# NMNSH_F-16_Lighting_Controller.net
KiCad netlist of a schematic drawn in EAGLE
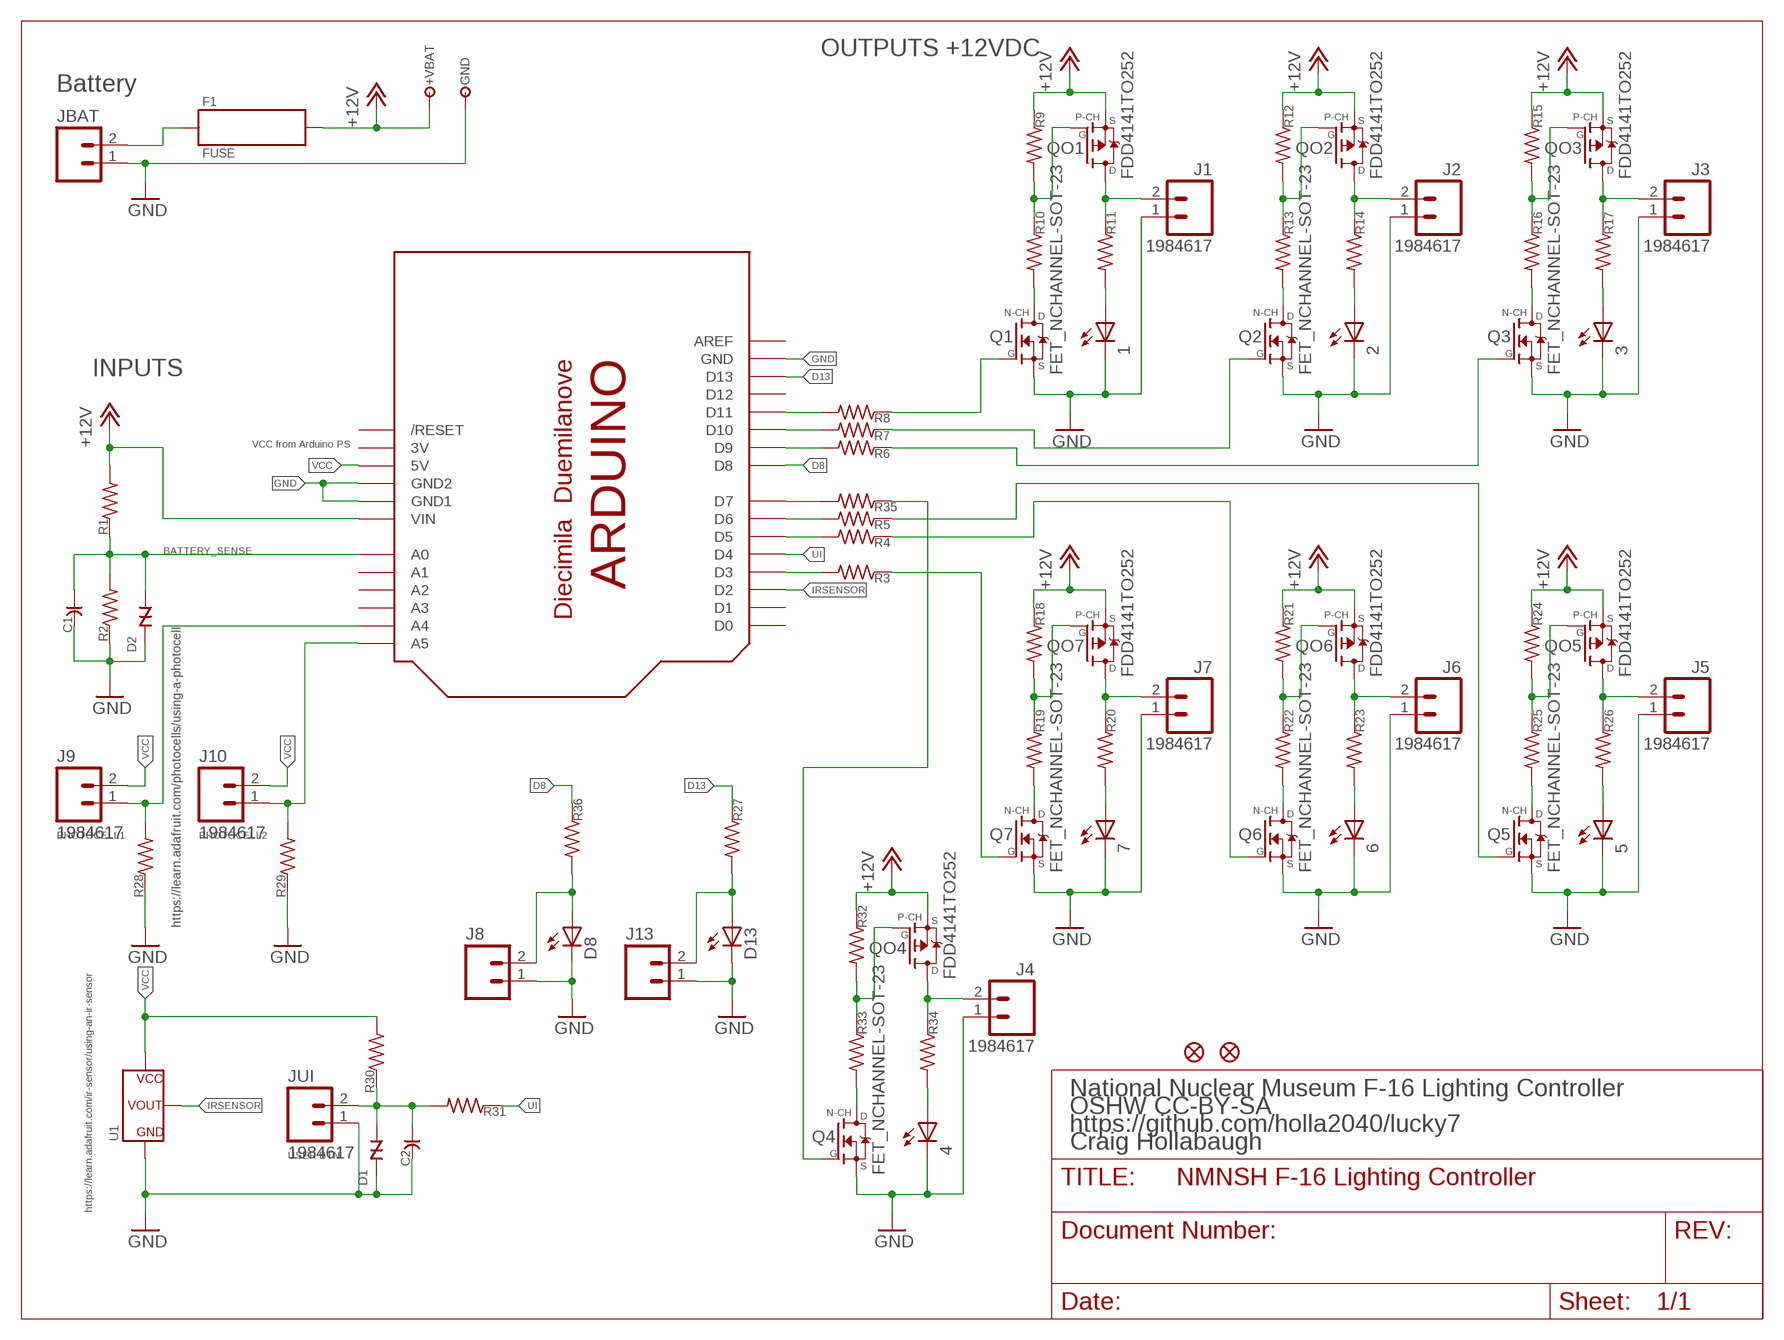
[diagram p0: schematic, sheet 1]

(export (version "E")
  (design (tool "Eeschema 10.0.6"))
  (components
    (comp (ref "+VBAT")
      (value "TESTPOINTTHRU")
      (footprint "eagle-import:TPTHRU")
      (libsource (lib "eagle-import") (part "TESTPOINTTHRU"))
    )
    (comp (ref "1")
      (value "LEDCHIP-LED0805")
      (footprint "eagle-import:CHIP-LED0805")
      (libsource (lib "eagle-import") (part "LEDCHIP-LED0805"))
    )
    (comp (ref "2")
      (value "LEDCHIP-LED0805")
      (footprint "eagle-import:CHIP-LED0805")
      (libsource (lib "eagle-import") (part "LEDCHIP-LED0805"))
    )
    (comp (ref "3")
      (value "LEDCHIP-LED0805")
      (footprint "eagle-import:CHIP-LED0805")
      (libsource (lib "eagle-import") (part "LEDCHIP-LED0805"))
    )
    (comp (ref "4")
      (value "LEDCHIP-LED0805")
      (footprint "eagle-import:CHIP-LED0805")
      (libsource (lib "eagle-import") (part "LEDCHIP-LED0805"))
    )
    (comp (ref "5")
      (value "LEDCHIP-LED0805")
      (footprint "eagle-import:CHIP-LED0805")
      (libsource (lib "eagle-import") (part "LEDCHIP-LED0805"))
    )
    (comp (ref "6")
      (value "LEDCHIP-LED0805")
      (footprint "eagle-import:CHIP-LED0805")
      (libsource (lib "eagle-import") (part "LEDCHIP-LED0805"))
    )
    (comp (ref "7")
      (value "LEDCHIP-LED0805")
      (footprint "eagle-import:CHIP-LED0805")
      (libsource (lib "eagle-import") (part "LEDCHIP-LED0805"))
    )
    (comp (ref "C1")
      (value "C-USC0603")
      (footprint "eagle-import:C0603")
      (libsource (lib "eagle-import") (part "C-USC0603"))
    )
    (comp (ref "C2")
      (value "C-USC0603")
      (footprint "eagle-import:C0603")
      (libsource (lib "eagle-import") (part "C-USC0603"))
    )
    (comp (ref "D1")
      (value "TVS0603")
      (footprint "eagle-import:TVS-0603")
      (libsource (lib "eagle-import") (part "TVS0603"))
    )
    (comp (ref "D2")
      (value "TVS0603")
      (footprint "eagle-import:TVS-0603")
      (libsource (lib "eagle-import") (part "TVS0603"))
    )
    (comp (ref "D8")
      (value "LEDCHIP-LED0805")
      (footprint "eagle-import:CHIP-LED0805")
      (libsource (lib "eagle-import") (part "LEDCHIP-LED0805"))
    )
    (comp (ref "D13")
      (value "LEDCHIP-LED0805")
      (footprint "eagle-import:CHIP-LED0805")
      (libsource (lib "eagle-import") (part "LEDCHIP-LED0805"))
    )
    (comp (ref "F1")
      (value "FUSE")
      (footprint "eagle-import:FUSE-3557-2")
      (libsource (lib "eagle-import") (part "FUSE"))
    )
    (comp (ref "GND")
      (value "TESTPOINTTHRU")
      (footprint "eagle-import:TPTHRU")
      (libsource (lib "eagle-import") (part "TESTPOINTTHRU"))
    )
    (comp (ref "J1")
      (value "1984617")
      (footprint "eagle-import:1984617")
      (libsource (lib "eagle-import") (part "1984617"))
    )
    (comp (ref "J2")
      (value "1984617")
      (footprint "eagle-import:1984617")
      (libsource (lib "eagle-import") (part "1984617"))
    )
    (comp (ref "J3")
      (value "1984617")
      (footprint "eagle-import:1984617")
      (libsource (lib "eagle-import") (part "1984617"))
    )
    (comp (ref "J4")
      (value "1984617")
      (footprint "eagle-import:1984617")
      (libsource (lib "eagle-import") (part "1984617"))
    )
    (comp (ref "J5")
      (value "1984617")
      (footprint "eagle-import:1984617")
      (libsource (lib "eagle-import") (part "1984617"))
    )
    (comp (ref "J6")
      (value "1984617")
      (footprint "eagle-import:1984617")
      (libsource (lib "eagle-import") (part "1984617"))
    )
    (comp (ref "J7")
      (value "1984617")
      (footprint "eagle-import:1984617")
      (libsource (lib "eagle-import") (part "1984617"))
    )
    (comp (ref "J8")
      (value "M02-0.1")
      (footprint "eagle-import:1X02")
      (libsource (lib "eagle-import") (part "M02-0.1"))
    )
    (comp (ref "J9")
      (value "1984617")
      (footprint "eagle-import:1984617")
      (libsource (lib "eagle-import") (part "1984617"))
    )
    (comp (ref "J10")
      (value "1984617")
      (footprint "eagle-import:1984617")
      (libsource (lib "eagle-import") (part "1984617"))
    )
    (comp (ref "J13")
      (value "M02-0.1")
      (footprint "eagle-import:1X02")
      (libsource (lib "eagle-import") (part "M02-0.1"))
    )
    (comp (ref "JBAT")
      (value "M02-6.35MM")
      (footprint "eagle-import:OSTT702")
      (libsource (lib "eagle-import") (part "M02-6.35MM"))
    )
    (comp (ref "JP1")
      (value "FIDUCIAL1X2")
      (footprint "eagle-import:FIDUCIAL-1X2")
      (libsource (lib "eagle-import") (part "FIDUCIAL1X2"))
    )
    (comp (ref "JP2")
      (value "FIDUCIAL1X2")
      (footprint "eagle-import:FIDUCIAL-1X2")
      (libsource (lib "eagle-import") (part "FIDUCIAL1X2"))
    )
    (comp (ref "JUI")
      (value "1984617")
      (footprint "eagle-import:1984617")
      (libsource (lib "eagle-import") (part "1984617"))
    )
    (comp (ref "Q1")
      (value "FET_NCHANNEL-SOT-23")
      (footprint "eagle-import:SOT-23")
      (libsource (lib "eagle-import") (part "FET_NCHANNEL-SOT-23"))
    )
    (comp (ref "Q2")
      (value "FET_NCHANNEL-SOT-23")
      (footprint "eagle-import:SOT-23")
      (libsource (lib "eagle-import") (part "FET_NCHANNEL-SOT-23"))
    )
    (comp (ref "Q3")
      (value "FET_NCHANNEL-SOT-23")
      (footprint "eagle-import:SOT-23")
      (libsource (lib "eagle-import") (part "FET_NCHANNEL-SOT-23"))
    )
    (comp (ref "Q4")
      (value "FET_NCHANNEL-SOT-23")
      (footprint "eagle-import:SOT-23")
      (libsource (lib "eagle-import") (part "FET_NCHANNEL-SOT-23"))
    )
    (comp (ref "Q5")
      (value "FET_NCHANNEL-SOT-23")
      (footprint "eagle-import:SOT-23")
      (libsource (lib "eagle-import") (part "FET_NCHANNEL-SOT-23"))
    )
    (comp (ref "Q6")
      (value "FET_NCHANNEL-SOT-23")
      (footprint "eagle-import:SOT-23")
      (libsource (lib "eagle-import") (part "FET_NCHANNEL-SOT-23"))
    )
    (comp (ref "Q7")
      (value "FET_NCHANNEL-SOT-23")
      (footprint "eagle-import:SOT-23")
      (libsource (lib "eagle-import") (part "FET_NCHANNEL-SOT-23"))
    )
    (comp (ref "QO1")
      (value "FDD4141TO252")
      (footprint "eagle-import:TO252")
      (libsource (lib "eagle-import") (part "FDD4141TO252"))
    )
    (comp (ref "QO2")
      (value "FDD4141TO252")
      (footprint "eagle-import:TO252")
      (libsource (lib "eagle-import") (part "FDD4141TO252"))
    )
    (comp (ref "QO3")
      (value "FDD4141TO252")
      (footprint "eagle-import:TO252")
      (libsource (lib "eagle-import") (part "FDD4141TO252"))
    )
    (comp (ref "QO4")
      (value "FDD4141TO252")
      (footprint "eagle-import:TO252")
      (libsource (lib "eagle-import") (part "FDD4141TO252"))
    )
    (comp (ref "QO5")
      (value "FDD4141TO252")
      (footprint "eagle-import:TO252")
      (libsource (lib "eagle-import") (part "FDD4141TO252"))
    )
    (comp (ref "QO6")
      (value "FDD4141TO252")
      (footprint "eagle-import:TO252")
      (libsource (lib "eagle-import") (part "FDD4141TO252"))
    )
    (comp (ref "QO7")
      (value "FDD4141TO252")
      (footprint "eagle-import:TO252")
      (libsource (lib "eagle-import") (part "FDD4141TO252"))
    )
    (comp (ref "R1")
      (value "R-US_R0603")
      (footprint "eagle-import:R0603")
      (libsource (lib "eagle-import") (part "R-US_R0603"))
    )
    (comp (ref "R2")
      (value "R-US_R0603")
      (footprint "eagle-import:R0603")
      (libsource (lib "eagle-import") (part "R-US_R0603"))
    )
    (comp (ref "R3")
      (value "R-US_R0603")
      (footprint "eagle-import:R0603")
      (libsource (lib "eagle-import") (part "R-US_R0603"))
    )
    (comp (ref "R4")
      (value "R-US_R0603")
      (footprint "eagle-import:R0603")
      (libsource (lib "eagle-import") (part "R-US_R0603"))
    )
    (comp (ref "R5")
      (value "R-US_R0603")
      (footprint "eagle-import:R0603")
      (libsource (lib "eagle-import") (part "R-US_R0603"))
    )
    (comp (ref "R6")
      (value "R-US_R0603")
      (footprint "eagle-import:R0603")
      (libsource (lib "eagle-import") (part "R-US_R0603"))
    )
    (comp (ref "R7")
      (value "R-US_R0603")
      (footprint "eagle-import:R0603")
      (libsource (lib "eagle-import") (part "R-US_R0603"))
    )
    (comp (ref "R8")
      (value "R-US_R0603")
      (footprint "eagle-import:R0603")
      (libsource (lib "eagle-import") (part "R-US_R0603"))
    )
    (comp (ref "R9")
      (value "R-US_R0603")
      (footprint "eagle-import:R0603")
      (libsource (lib "eagle-import") (part "R-US_R0603"))
    )
    (comp (ref "R10")
      (value "R-US_R0603")
      (footprint "eagle-import:R0603")
      (libsource (lib "eagle-import") (part "R-US_R0603"))
    )
    (comp (ref "R11")
      (value "R-US_R0603")
      (footprint "eagle-import:R0603")
      (libsource (lib "eagle-import") (part "R-US_R0603"))
    )
    (comp (ref "R12")
      (value "R-US_R0603")
      (footprint "eagle-import:R0603")
      (libsource (lib "eagle-import") (part "R-US_R0603"))
    )
    (comp (ref "R13")
      (value "R-US_R0603")
      (footprint "eagle-import:R0603")
      (libsource (lib "eagle-import") (part "R-US_R0603"))
    )
    (comp (ref "R14")
      (value "R-US_R0603")
      (footprint "eagle-import:R0603")
      (libsource (lib "eagle-import") (part "R-US_R0603"))
    )
    (comp (ref "R15")
      (value "R-US_R0603")
      (footprint "eagle-import:R0603")
      (libsource (lib "eagle-import") (part "R-US_R0603"))
    )
    (comp (ref "R16")
      (value "R-US_R0603")
      (footprint "eagle-import:R0603")
      (libsource (lib "eagle-import") (part "R-US_R0603"))
    )
    (comp (ref "R17")
      (value "R-US_R0603")
      (footprint "eagle-import:R0603")
      (libsource (lib "eagle-import") (part "R-US_R0603"))
    )
    (comp (ref "R18")
      (value "R-US_R0603")
      (footprint "eagle-import:R0603")
      (libsource (lib "eagle-import") (part "R-US_R0603"))
    )
    (comp (ref "R19")
      (value "R-US_R0603")
      (footprint "eagle-import:R0603")
      (libsource (lib "eagle-import") (part "R-US_R0603"))
    )
    (comp (ref "R20")
      (value "R-US_R0603")
      (footprint "eagle-import:R0603")
      (libsource (lib "eagle-import") (part "R-US_R0603"))
    )
    (comp (ref "R21")
      (value "R-US_R0603")
      (footprint "eagle-import:R0603")
      (libsource (lib "eagle-import") (part "R-US_R0603"))
    )
    (comp (ref "R22")
      (value "R-US_R0603")
      (footprint "eagle-import:R0603")
      (libsource (lib "eagle-import") (part "R-US_R0603"))
    )
    (comp (ref "R23")
      (value "R-US_R0603")
      (footprint "eagle-import:R0603")
      (libsource (lib "eagle-import") (part "R-US_R0603"))
    )
    (comp (ref "R24")
      (value "R-US_R0603")
      (footprint "eagle-import:R0603")
      (libsource (lib "eagle-import") (part "R-US_R0603"))
    )
    (comp (ref "R25")
      (value "R-US_R0603")
      (footprint "eagle-import:R0603")
      (libsource (lib "eagle-import") (part "R-US_R0603"))
    )
    (comp (ref "R26")
      (value "R-US_R0603")
      (footprint "eagle-import:R0603")
      (libsource (lib "eagle-import") (part "R-US_R0603"))
    )
    (comp (ref "R27")
      (value "R-US_R0603")
      (footprint "eagle-import:R0603")
      (libsource (lib "eagle-import") (part "R-US_R0603"))
    )
    (comp (ref "R28")
      (value "R-US_R0603")
      (footprint "eagle-import:R0603")
      (libsource (lib "eagle-import") (part "R-US_R0603"))
    )
    (comp (ref "R29")
      (value "R-US_R0603")
      (footprint "eagle-import:R0603")
      (libsource (lib "eagle-import") (part "R-US_R0603"))
    )
    (comp (ref "R30")
      (value "R-US_R0603")
      (footprint "eagle-import:R0603")
      (libsource (lib "eagle-import") (part "R-US_R0603"))
    )
    (comp (ref "R31")
      (value "R-US_R0603")
      (footprint "eagle-import:R0603")
      (libsource (lib "eagle-import") (part "R-US_R0603"))
    )
    (comp (ref "R32")
      (value "R-US_R0603")
      (footprint "eagle-import:R0603")
      (libsource (lib "eagle-import") (part "R-US_R0603"))
    )
    (comp (ref "R33")
      (value "R-US_R0603")
      (footprint "eagle-import:R0603")
      (libsource (lib "eagle-import") (part "R-US_R0603"))
    )
    (comp (ref "R34")
      (value "R-US_R0603")
      (footprint "eagle-import:R0603")
      (libsource (lib "eagle-import") (part "R-US_R0603"))
    )
    (comp (ref "R35")
      (value "R-US_R0603")
      (footprint "eagle-import:R0603")
      (libsource (lib "eagle-import") (part "R-US_R0603"))
    )
    (comp (ref "R36")
      (value "R-US_R0603")
      (footprint "eagle-import:R0603")
      (libsource (lib "eagle-import") (part "R-US_R0603"))
    )
    (comp (ref "U1")
      (value "IRDETECTOR-THRU")
      (footprint "eagle-import:IRDETECTOR-THRU")
      (libsource (lib "eagle-import") (part "IRDETECTOR-THRU"))
    )
    (comp (ref "U100")
      (value "ARDUINO-BPLACE")
      (footprint "eagle-import:ARDUINO-BPLACE")
      (libsource (lib "eagle-import") (part "ARDUINO-BPLACE"))
    )
  )
  (nets
    (net (code "1") (name "+12V") (class "Default")
      (node (ref "+VBAT") (pin "1") (pinfunction "P$1_1") (pintype "bidirectional"))
      (node (ref "F1") (pin "2@1") (pinfunction "P$2_2@1") (pintype "bidirectional"))
      (node (ref "F1") (pin "2@2") (pinfunction "P$2_2@2") (pintype "bidirectional"))
      (node (ref "QO1") (pin "2") (pinfunction "S_2") (pintype "passive"))
      (node (ref "QO2") (pin "2") (pinfunction "S_2") (pintype "passive"))
      (node (ref "QO3") (pin "2") (pinfunction "S_2") (pintype "passive"))
      (node (ref "QO4") (pin "2") (pinfunction "S_2") (pintype "passive"))
      (node (ref "QO5") (pin "2") (pinfunction "S_2") (pintype "passive"))
      (node (ref "QO6") (pin "2") (pinfunction "S_2") (pintype "passive"))
      (node (ref "QO7") (pin "2") (pinfunction "S_2") (pintype "passive"))
      (node (ref "R1") (pin "2") (pinfunction "2_2") (pintype "passive"))
      (node (ref "R12") (pin "1") (pinfunction "1_1") (pintype "passive"))
      (node (ref "R15") (pin "1") (pinfunction "1_1") (pintype "passive"))
      (node (ref "R18") (pin "1") (pinfunction "1_1") (pintype "passive"))
      (node (ref "R21") (pin "1") (pinfunction "1_1") (pintype "passive"))
      (node (ref "R24") (pin "1") (pinfunction "1_1") (pintype "passive"))
      (node (ref "R32") (pin "1") (pinfunction "1_1") (pintype "passive"))
      (node (ref "R9") (pin "1") (pinfunction "1_1") (pintype "passive"))
      (node (ref "U100") (pin "VIN") (pinfunction "VIN_VIN") (pintype "power_in"))
    )
    (net (code "2") (name "/3V") (class "Default")
      (node (ref "U100") (pin "3V") (pinfunction "3V_3V") (pintype "power_in"))
    )
    (net (code "3") (name "/BATTERY_SENSE") (class "Default")
      (node (ref "C1") (pin "1") (pinfunction "1_1") (pintype "passive"))
      (node (ref "D2") (pin "1") (pinfunction "1_1") (pintype "bidirectional"))
      (node (ref "R1") (pin "1") (pinfunction "1_1") (pintype "passive"))
      (node (ref "R2") (pin "2") (pinfunction "2_2") (pintype "passive"))
      (node (ref "U100") (pin "A0") (pinfunction "A0_A0") (pintype "bidirectional"))
    )
    (net (code "4") (name "D8") (class "Default")
      (node (ref "R36") (pin "1") (pinfunction "1_1") (pintype "passive"))
      (node (ref "U100") (pin "D8") (pinfunction "D8_D8") (pintype "bidirectional"))
    )
    (net (code "5") (name "D13") (class "Default")
      (node (ref "R27") (pin "1") (pinfunction "1_1") (pintype "passive"))
      (node (ref "U100") (pin "D13") (pinfunction "D13_D13") (pintype "bidirectional"))
    )
    (net (code "6") (name "GND") (class "Default")
      (node (ref "1") (pin "C") (pinfunction "C_C") (pintype "passive"))
      (node (ref "2") (pin "C") (pinfunction "C_C") (pintype "passive"))
      (node (ref "3") (pin "C") (pinfunction "C_C") (pintype "passive"))
      (node (ref "4") (pin "C") (pinfunction "C_C") (pintype "passive"))
      (node (ref "5") (pin "C") (pinfunction "C_C") (pintype "passive"))
      (node (ref "6") (pin "C") (pinfunction "C_C") (pintype "passive"))
      (node (ref "7") (pin "C") (pinfunction "C_C") (pintype "passive"))
      (node (ref "C1") (pin "2") (pinfunction "2_2") (pintype "passive"))
      (node (ref "C2") (pin "2") (pinfunction "2_2") (pintype "passive"))
      (node (ref "D1") (pin "2") (pinfunction "2_2") (pintype "bidirectional"))
      (node (ref "D13") (pin "C") (pinfunction "C_C") (pintype "passive"))
      (node (ref "D2") (pin "2") (pinfunction "2_2") (pintype "bidirectional"))
      (node (ref "D8") (pin "C") (pinfunction "C_C") (pintype "passive"))
      (node (ref "GND") (pin "1") (pinfunction "P$1_1") (pintype "bidirectional"))
      (node (ref "J1") (pin "1") (pinfunction "1_1") (pintype "passive"))
      (node (ref "J13") (pin "1") (pinfunction "1_1") (pintype "passive"))
      (node (ref "J2") (pin "1") (pinfunction "1_1") (pintype "passive"))
      (node (ref "J3") (pin "1") (pinfunction "1_1") (pintype "passive"))
      (node (ref "J4") (pin "1") (pinfunction "1_1") (pintype "passive"))
      (node (ref "J5") (pin "1") (pinfunction "1_1") (pintype "passive"))
      (node (ref "J6") (pin "1") (pinfunction "1_1") (pintype "passive"))
      (node (ref "J7") (pin "1") (pinfunction "1_1") (pintype "passive"))
      (node (ref "J8") (pin "1") (pinfunction "1_1") (pintype "passive"))
      (node (ref "JBAT") (pin "1") (pinfunction "1_1") (pintype "passive"))
      (node (ref "JUI") (pin "1") (pinfunction "1_1") (pintype "passive"))
      (node (ref "Q1") (pin "3") (pinfunction "S_3") (pintype "passive"))
      (node (ref "Q2") (pin "3") (pinfunction "S_3") (pintype "passive"))
      (node (ref "Q3") (pin "3") (pinfunction "S_3") (pintype "passive"))
      (node (ref "Q4") (pin "3") (pinfunction "S_3") (pintype "passive"))
      (node (ref "Q5") (pin "3") (pinfunction "S_3") (pintype "passive"))
      (node (ref "Q6") (pin "3") (pinfunction "S_3") (pintype "passive"))
      (node (ref "Q7") (pin "3") (pinfunction "S_3") (pintype "passive"))
      (node (ref "R2") (pin "1") (pinfunction "1_1") (pintype "passive"))
      (node (ref "R28") (pin "1") (pinfunction "1_1") (pintype "passive"))
      (node (ref "R29") (pin "1") (pinfunction "1_1") (pintype "passive"))
      (node (ref "U1") (pin "GND") (pinfunction "GND_GND") (pintype "bidirectional"))
      (node (ref "U100") (pin "GND") (pinfunction "GND_GND") (pintype "power_in"))
      (node (ref "U100") (pin "GND1") (pinfunction "GND1_GND1") (pintype "power_in"))
      (node (ref "U100") (pin "GND2") (pinfunction "GND2_GND2") (pintype "power_in"))
    )
    (net (code "7") (name "IRSENSOR") (class "Default")
      (node (ref "U1") (pin "VOUT") (pinfunction "VOUT_VOUT") (pintype "bidirectional"))
      (node (ref "U100") (pin "D2") (pinfunction "D2_D2") (pintype "bidirectional"))
    )
    (net (code "8") (name "Net-(1-PadA)") (class "Default")
      (node (ref "1") (pin "A") (pinfunction "A_A") (pintype "passive"))
      (node (ref "R11") (pin "2") (pinfunction "2_2") (pintype "passive"))
    )
    (net (code "9") (name "Net-(2-PadA)") (class "Default")
      (node (ref "2") (pin "A") (pinfunction "A_A") (pintype "passive"))
      (node (ref "R14") (pin "2") (pinfunction "2_2") (pintype "passive"))
    )
    (net (code "10") (name "Net-(3-PadA)") (class "Default")
      (node (ref "3") (pin "A") (pinfunction "A_A") (pintype "passive"))
      (node (ref "R17") (pin "2") (pinfunction "2_2") (pintype "passive"))
    )
    (net (code "11") (name "Net-(4-PadA)") (class "Default")
      (node (ref "4") (pin "A") (pinfunction "A_A") (pintype "passive"))
      (node (ref "R34") (pin "2") (pinfunction "2_2") (pintype "passive"))
    )
    (net (code "12") (name "Net-(5-PadA)") (class "Default")
      (node (ref "5") (pin "A") (pinfunction "A_A") (pintype "passive"))
      (node (ref "R26") (pin "2") (pinfunction "2_2") (pintype "passive"))
    )
    (net (code "13") (name "Net-(6-PadA)") (class "Default")
      (node (ref "6") (pin "A") (pinfunction "A_A") (pintype "passive"))
      (node (ref "R23") (pin "2") (pinfunction "2_2") (pintype "passive"))
    )
    (net (code "14") (name "Net-(7-PadA)") (class "Default")
      (node (ref "7") (pin "A") (pinfunction "A_A") (pintype "passive"))
      (node (ref "R20") (pin "2") (pinfunction "2_2") (pintype "passive"))
    )
    (net (code "15") (name "Net-(C2-Pad1)") (class "Default")
      (node (ref "C2") (pin "1") (pinfunction "1_1") (pintype "passive"))
      (node (ref "D1") (pin "1") (pinfunction "1_1") (pintype "bidirectional"))
      (node (ref "JUI") (pin "2") (pinfunction "2_2") (pintype "passive"))
      (node (ref "R30") (pin "1") (pinfunction "1_1") (pintype "passive"))
      (node (ref "R31") (pin "2") (pinfunction "2_2") (pintype "passive"))
    )
    (net (code "16") (name "Net-(D8-PadA)") (class "Default")
      (node (ref "D8") (pin "A") (pinfunction "A_A") (pintype "passive"))
      (node (ref "J8") (pin "2") (pinfunction "2_2") (pintype "passive"))
      (node (ref "R36") (pin "2") (pinfunction "2_2") (pintype "passive"))
    )
    (net (code "17") (name "Net-(D13-PadA)") (class "Default")
      (node (ref "D13") (pin "A") (pinfunction "A_A") (pintype "passive"))
      (node (ref "J13") (pin "2") (pinfunction "2_2") (pintype "passive"))
      (node (ref "R27") (pin "2") (pinfunction "2_2") (pintype "passive"))
    )
    (net (code "18") (name "Net-(F1-P$1-Pad1@1)") (class "Default")
      (node (ref "F1") (pin "1@1") (pinfunction "P$1_1@1") (pintype "bidirectional"))
      (node (ref "F1") (pin "1@2") (pinfunction "P$1_1@2") (pintype "bidirectional"))
      (node (ref "JBAT") (pin "2") (pinfunction "2_2") (pintype "passive"))
    )
    (net (code "19") (name "Net-(J9-Pad1)") (class "Default")
      (node (ref "J9") (pin "1") (pinfunction "1_1") (pintype "passive"))
      (node (ref "R28") (pin "2") (pinfunction "2_2") (pintype "passive"))
      (node (ref "U100") (pin "A4") (pinfunction "A4_A4") (pintype "bidirectional"))
    )
    (net (code "20") (name "Net-(J10-Pad1)") (class "Default")
      (node (ref "J10") (pin "1") (pinfunction "1_1") (pintype "passive"))
      (node (ref "R29") (pin "2") (pinfunction "2_2") (pintype "passive"))
      (node (ref "U100") (pin "A5") (pinfunction "A5_A5") (pintype "bidirectional"))
    )
    (net (code "21") (name "Net-(Q1-D)") (class "Default")
      (node (ref "Q1") (pin "1") (pinfunction "D_1") (pintype "passive"))
      (node (ref "R10") (pin "2") (pinfunction "2_2") (pintype "passive"))
    )
    (net (code "22") (name "Net-(Q1-G)") (class "Default")
      (node (ref "Q1") (pin "2") (pinfunction "G_2") (pintype "passive"))
      (node (ref "R8") (pin "1") (pinfunction "1_1") (pintype "passive"))
    )
    (net (code "23") (name "Net-(Q2-D)") (class "Default")
      (node (ref "Q2") (pin "1") (pinfunction "D_1") (pintype "passive"))
      (node (ref "R13") (pin "2") (pinfunction "2_2") (pintype "passive"))
    )
    (net (code "24") (name "Net-(Q2-G)") (class "Default")
      (node (ref "Q2") (pin "2") (pinfunction "G_2") (pintype "passive"))
      (node (ref "R7") (pin "1") (pinfunction "1_1") (pintype "passive"))
    )
    (net (code "25") (name "Net-(Q3-D)") (class "Default")
      (node (ref "Q3") (pin "1") (pinfunction "D_1") (pintype "passive"))
      (node (ref "R16") (pin "2") (pinfunction "2_2") (pintype "passive"))
    )
    (net (code "26") (name "Net-(Q3-G)") (class "Default")
      (node (ref "Q3") (pin "2") (pinfunction "G_2") (pintype "passive"))
      (node (ref "R6") (pin "1") (pinfunction "1_1") (pintype "passive"))
    )
    (net (code "27") (name "Net-(Q4-D)") (class "Default")
      (node (ref "Q4") (pin "1") (pinfunction "D_1") (pintype "passive"))
      (node (ref "R33") (pin "2") (pinfunction "2_2") (pintype "passive"))
    )
    (net (code "28") (name "Net-(Q4-G)") (class "Default")
      (node (ref "Q4") (pin "2") (pinfunction "G_2") (pintype "passive"))
      (node (ref "R35") (pin "1") (pinfunction "1_1") (pintype "passive"))
    )
    (net (code "29") (name "Net-(Q5-D)") (class "Default")
      (node (ref "Q5") (pin "1") (pinfunction "D_1") (pintype "passive"))
      (node (ref "R25") (pin "2") (pinfunction "2_2") (pintype "passive"))
    )
    (net (code "30") (name "Net-(Q5-G)") (class "Default")
      (node (ref "Q5") (pin "2") (pinfunction "G_2") (pintype "passive"))
      (node (ref "R5") (pin "1") (pinfunction "1_1") (pintype "passive"))
    )
    (net (code "31") (name "Net-(Q6-D)") (class "Default")
      (node (ref "Q6") (pin "1") (pinfunction "D_1") (pintype "passive"))
      (node (ref "R22") (pin "2") (pinfunction "2_2") (pintype "passive"))
    )
    (net (code "32") (name "Net-(Q6-G)") (class "Default")
      (node (ref "Q6") (pin "2") (pinfunction "G_2") (pintype "passive"))
      (node (ref "R4") (pin "1") (pinfunction "1_1") (pintype "passive"))
    )
    (net (code "33") (name "Net-(Q7-D)") (class "Default")
      (node (ref "Q7") (pin "1") (pinfunction "D_1") (pintype "passive"))
      (node (ref "R19") (pin "2") (pinfunction "2_2") (pintype "passive"))
    )
    (net (code "34") (name "Net-(Q7-G)") (class "Default")
      (node (ref "Q7") (pin "2") (pinfunction "G_2") (pintype "passive"))
      (node (ref "R3") (pin "1") (pinfunction "1_1") (pintype "passive"))
    )
    (net (code "35") (name "Net-(QO1-D)") (class "Default")
      (node (ref "J1") (pin "2") (pinfunction "2_2") (pintype "passive"))
      (node (ref "QO1") (pin "3") (pinfunction "D_3") (pintype "passive"))
      (node (ref "R11") (pin "1") (pinfunction "1_1") (pintype "passive"))
    )
    (net (code "36") (name "Net-(QO1-G)") (class "Default")
      (node (ref "QO1") (pin "1") (pinfunction "G_1") (pintype "passive"))
      (node (ref "R10") (pin "1") (pinfunction "1_1") (pintype "passive"))
      (node (ref "R9") (pin "2") (pinfunction "2_2") (pintype "passive"))
    )
    (net (code "37") (name "Net-(QO2-D)") (class "Default")
      (node (ref "J2") (pin "2") (pinfunction "2_2") (pintype "passive"))
      (node (ref "QO2") (pin "3") (pinfunction "D_3") (pintype "passive"))
      (node (ref "R14") (pin "1") (pinfunction "1_1") (pintype "passive"))
    )
    (net (code "38") (name "Net-(QO2-G)") (class "Default")
      (node (ref "QO2") (pin "1") (pinfunction "G_1") (pintype "passive"))
      (node (ref "R12") (pin "2") (pinfunction "2_2") (pintype "passive"))
      (node (ref "R13") (pin "1") (pinfunction "1_1") (pintype "passive"))
    )
    (net (code "39") (name "Net-(QO3-D)") (class "Default")
      (node (ref "J3") (pin "2") (pinfunction "2_2") (pintype "passive"))
      (node (ref "QO3") (pin "3") (pinfunction "D_3") (pintype "passive"))
      (node (ref "R17") (pin "1") (pinfunction "1_1") (pintype "passive"))
    )
    (net (code "40") (name "Net-(QO3-G)") (class "Default")
      (node (ref "QO3") (pin "1") (pinfunction "G_1") (pintype "passive"))
      (node (ref "R15") (pin "2") (pinfunction "2_2") (pintype "passive"))
      (node (ref "R16") (pin "1") (pinfunction "1_1") (pintype "passive"))
    )
    (net (code "41") (name "Net-(QO4-D)") (class "Default")
      (node (ref "J4") (pin "2") (pinfunction "2_2") (pintype "passive"))
      (node (ref "QO4") (pin "3") (pinfunction "D_3") (pintype "passive"))
      (node (ref "R34") (pin "1") (pinfunction "1_1") (pintype "passive"))
    )
    (net (code "42") (name "Net-(QO4-G)") (class "Default")
      (node (ref "QO4") (pin "1") (pinfunction "G_1") (pintype "passive"))
      (node (ref "R32") (pin "2") (pinfunction "2_2") (pintype "passive"))
      (node (ref "R33") (pin "1") (pinfunction "1_1") (pintype "passive"))
    )
    (net (code "43") (name "Net-(QO5-D)") (class "Default")
      (node (ref "J5") (pin "2") (pinfunction "2_2") (pintype "passive"))
      (node (ref "QO5") (pin "3") (pinfunction "D_3") (pintype "passive"))
      (node (ref "R26") (pin "1") (pinfunction "1_1") (pintype "passive"))
    )
    (net (code "44") (name "Net-(QO5-G)") (class "Default")
      (node (ref "QO5") (pin "1") (pinfunction "G_1") (pintype "passive"))
      (node (ref "R24") (pin "2") (pinfunction "2_2") (pintype "passive"))
      (node (ref "R25") (pin "1") (pinfunction "1_1") (pintype "passive"))
    )
    (net (code "45") (name "Net-(QO6-D)") (class "Default")
      (node (ref "J6") (pin "2") (pinfunction "2_2") (pintype "passive"))
      (node (ref "QO6") (pin "3") (pinfunction "D_3") (pintype "passive"))
      (node (ref "R23") (pin "1") (pinfunction "1_1") (pintype "passive"))
    )
    (net (code "46") (name "Net-(QO6-G)") (class "Default")
      (node (ref "QO6") (pin "1") (pinfunction "G_1") (pintype "passive"))
      (node (ref "R21") (pin "2") (pinfunction "2_2") (pintype "passive"))
      (node (ref "R22") (pin "1") (pinfunction "1_1") (pintype "passive"))
    )
    (net (code "47") (name "Net-(QO7-D)") (class "Default")
      (node (ref "J7") (pin "2") (pinfunction "2_2") (pintype "passive"))
      (node (ref "QO7") (pin "3") (pinfunction "D_3") (pintype "passive"))
      (node (ref "R20") (pin "1") (pinfunction "1_1") (pintype "passive"))
    )
    (net (code "48") (name "Net-(QO7-G)") (class "Default")
      (node (ref "QO7") (pin "1") (pinfunction "G_1") (pintype "passive"))
      (node (ref "R18") (pin "2") (pinfunction "2_2") (pintype "passive"))
      (node (ref "R19") (pin "1") (pinfunction "1_1") (pintype "passive"))
    )
    (net (code "49") (name "Net-(R3-Pad2)") (class "Default")
      (node (ref "R3") (pin "2") (pinfunction "2_2") (pintype "passive"))
      (node (ref "U100") (pin "D3") (pinfunction "D3_D3") (pintype "bidirectional"))
    )
    (net (code "50") (name "Net-(R4-Pad2)") (class "Default")
      (node (ref "R4") (pin "2") (pinfunction "2_2") (pintype "passive"))
      (node (ref "U100") (pin "D5") (pinfunction "D5_D5") (pintype "bidirectional"))
    )
    (net (code "51") (name "Net-(R5-Pad2)") (class "Default")
      (node (ref "R5") (pin "2") (pinfunction "2_2") (pintype "passive"))
      (node (ref "U100") (pin "D6") (pinfunction "D6_D6") (pintype "bidirectional"))
    )
    (net (code "52") (name "Net-(R6-Pad2)") (class "Default")
      (node (ref "R6") (pin "2") (pinfunction "2_2") (pintype "passive"))
      (node (ref "U100") (pin "D9") (pinfunction "D9_D9") (pintype "bidirectional"))
    )
    (net (code "53") (name "Net-(R7-Pad2)") (class "Default")
      (node (ref "R7") (pin "2") (pinfunction "2_2") (pintype "passive"))
      (node (ref "U100") (pin "D10") (pinfunction "D10_D10") (pintype "bidirectional"))
    )
    (net (code "54") (name "Net-(R8-Pad2)") (class "Default")
      (node (ref "R8") (pin "2") (pinfunction "2_2") (pintype "passive"))
      (node (ref "U100") (pin "D11") (pinfunction "D11_D11") (pintype "bidirectional"))
    )
    (net (code "55") (name "Net-(R35-Pad2)") (class "Default")
      (node (ref "R35") (pin "2") (pinfunction "2_2") (pintype "passive"))
      (node (ref "U100") (pin "D7") (pinfunction "D7_D7") (pintype "bidirectional"))
    )
    (net (code "56") (name "UI") (class "Default")
      (node (ref "R31") (pin "1") (pinfunction "1_1") (pintype "passive"))
      (node (ref "U100") (pin "D4") (pinfunction "D4_D4") (pintype "bidirectional"))
    )
    (net (code "57") (name "VCC") (class "Default")
      (node (ref "J10") (pin "2") (pinfunction "2_2") (pintype "passive"))
      (node (ref "J9") (pin "2") (pinfunction "2_2") (pintype "passive"))
      (node (ref "R30") (pin "2") (pinfunction "2_2") (pintype "passive"))
      (node (ref "U1") (pin "VCC") (pinfunction "VCC_VCC") (pintype "bidirectional"))
      (node (ref "U100") (pin "5V") (pinfunction "5V_5V") (pintype "power_in"))
    )
    (net (code "58") (name "unconnected-(U100-PadA1)") (class "Default")
      (node (ref "U100") (pin "A1") (pinfunction "A1_A1") (pintype "bidirectional"))
    )
    (net (code "59") (name "unconnected-(U100-PadA2)") (class "Default")
      (node (ref "U100") (pin "A2") (pinfunction "A2_A2") (pintype "bidirectional"))
    )
    (net (code "60") (name "unconnected-(U100-PadA3)") (class "Default")
      (node (ref "U100") (pin "A3") (pinfunction "A3_A3") (pintype "bidirectional"))
    )
    (net (code "61") (name "unconnected-(U100-PadAREF)") (class "Default")
      (node (ref "U100") (pin "AREF") (pinfunction "AREF_AREF") (pintype "bidirectional"))
    )
    (net (code "62") (name "unconnected-(U100-PadD0)") (class "Default")
      (node (ref "U100") (pin "D0") (pinfunction "D0_D0") (pintype "bidirectional"))
    )
    (net (code "63") (name "unconnected-(U100-PadD1)") (class "Default")
      (node (ref "U100") (pin "D1") (pinfunction "D1_D1") (pintype "bidirectional"))
    )
    (net (code "64") (name "unconnected-(U100-PadD12)") (class "Default")
      (node (ref "U100") (pin "D12") (pinfunction "D12_D12") (pintype "bidirectional"))
    )
    (net (code "65") (name "unconnected-(U100-{slash}RESET-PadRESET)") (class "Default")
      (node (ref "U100") (pin "RESET") (pinfunction "/RESET_RESET") (pintype "bidirectional"))
    )
  )
)
